# BMS-Shield_rev1.net
KiCad netlist of a schematic drawn in EAGLE
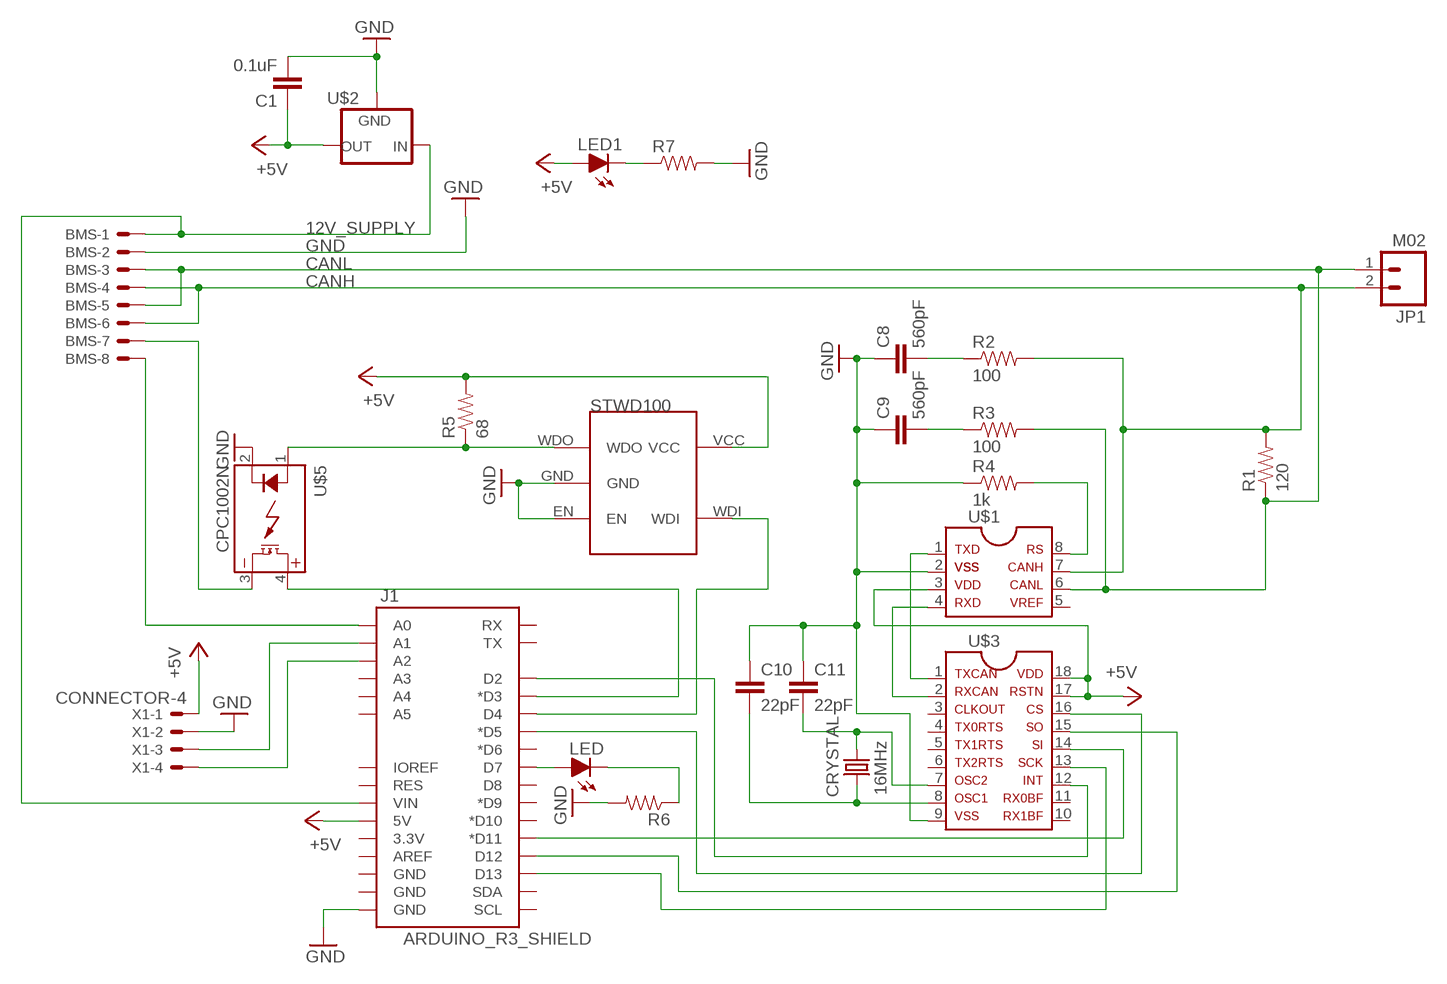
[diagram p0: schematic, sheet 1]

(export (version "E")
  (design (tool "Eeschema 10.0.6"))
  (components
    (comp (ref "BMS")
      (value "MINIFIT_5566-8")
      (footprint "eagle-import:MINIFIT_5566-8")
      (libsource (lib "eagle-import") (part "MINIFIT_5566-8"))
    )
    (comp (ref "C1")
      (value "0.1uF")
      (footprint "eagle-import:0805")
      (libsource (lib "eagle-import") (part "CAP0805"))
    )
    (comp (ref "C8")
      (value "560pF")
      (footprint "eagle-import:0805")
      (libsource (lib "eagle-import") (part "CAP0805"))
    )
    (comp (ref "C9")
      (value "560pF")
      (footprint "eagle-import:0805")
      (libsource (lib "eagle-import") (part "CAP0805"))
    )
    (comp (ref "C10")
      (value "22pF")
      (footprint "eagle-import:0805")
      (libsource (lib "eagle-import") (part "CAP0805"))
    )
    (comp (ref "C11")
      (value "22pF")
      (footprint "eagle-import:0805")
      (libsource (lib "eagle-import") (part "CAP0805"))
    )
    (comp (ref "CRYSTAL")
      (value "16MHz")
      (footprint "eagle-import:HC49UP")
      (libsource (lib "eagle-import") (part "CRYSTALSMD"))
    )
    (comp (ref "J1")
      (value "ARDUINO_R3_SHIELD")
      (footprint "eagle-import:UNO_R3_SHIELD")
      (libsource (lib "eagle-import") (part "ARDUINO_R3_SHIELD"))
    )
    (comp (ref "JP1")
      (value "M02")
      (footprint "eagle-import:1X02")
      (libsource (lib "eagle-import") (part "M02"))
    )
    (comp (ref "LED")
      (value "LED-0805")
      (footprint "eagle-import:LED-805")
      (libsource (lib "eagle-import") (part "LED-0805"))
    )
    (comp (ref "LED1")
      (value "LED-0805")
      (footprint "eagle-import:LED-805")
      (libsource (lib "eagle-import") (part "LED-0805"))
    )
    (comp (ref "R1")
      (value "120")
      (footprint "eagle-import:0805")
      (libsource (lib "eagle-import") (part "RESISTOR0805-RES"))
    )
    (comp (ref "R2")
      (value "100")
      (footprint "eagle-import:0805")
      (libsource (lib "eagle-import") (part "RESISTOR0805-RES"))
    )
    (comp (ref "R3")
      (value "100")
      (footprint "eagle-import:0805")
      (libsource (lib "eagle-import") (part "RESISTOR0805-RES"))
    )
    (comp (ref "R4")
      (value "1k")
      (footprint "eagle-import:0805")
      (libsource (lib "eagle-import") (part "RESISTOR0805-RES"))
    )
    (comp (ref "R5")
      (value "68")
      (footprint "eagle-import:0805")
      (libsource (lib "eagle-import") (part "RESISTOR0805-RES"))
    )
    (comp (ref "R6")
      (value "RESISTOR0805-RES")
      (footprint "eagle-import:0805")
      (libsource (lib "eagle-import") (part "RESISTOR0805-RES"))
    )
    (comp (ref "R7")
      (value "RESISTOR0805-RES")
      (footprint "eagle-import:0805")
      (libsource (lib "eagle-import") (part "RESISTOR0805-RES"))
    )
    (comp (ref "U$1")
      (value "MCP2551")
      (footprint "eagle-import:SOIC-08")
      (libsource (lib "eagle-import") (part "MCP2551"))
    )
    (comp (ref "U$2")
      (value "5VREG_LM340-NLM340MPX-5.0/NOPB")
      (footprint "eagle-import:SOT223")
      (libsource (lib "eagle-import") (part "5VREG_LM340-NLM340MPX-5.0/NOPB"))
    )
    (comp (ref "U$3")
      (value "MCP2515SMD")
      (footprint "eagle-import:SOIC-18W")
      (libsource (lib "eagle-import") (part "MCP2515SMD"))
    )
    (comp (ref "U$4")
      (value "STWD100")
      (footprint "eagle-import:SOT23-5")
      (libsource (lib "eagle-import") (part "STWD100"))
    )
    (comp (ref "U$5")
      (value "CPC1002N")
      (footprint "eagle-import:SOP04")
      (libsource (lib "eagle-import") (part "CPC1002N"))
    )
    (comp (ref "X1")
      (value "CONNECTOR-4")
      (footprint "eagle-import:MINIFIT_5566-4")
      (libsource (lib "eagle-import") (part "CONNECTOR-4"))
    )
  )
  (nets
    (net (code "1") (name "+5V") (class "Default")
      (node (ref "C1") (pin "1") (pinfunction "1_1") (pintype "passive"))
      (node (ref "J1") (pin "5V") (pinfunction "5V_5V") (pintype "bidirectional"))
      (node (ref "LED1") (pin "A") (pinfunction "A_A") (pintype "passive"))
      (node (ref "R5") (pin "2") (pinfunction "2_2") (pintype "passive"))
      (node (ref "U$1") (pin "3") (pinfunction "3_3") (pintype "passive"))
      (node (ref "U$2") (pin "3") (pinfunction "OUT_3") (pintype "output"))
      (node (ref "U$3") (pin "17") (pinfunction "17_17") (pintype "passive"))
      (node (ref "U$3") (pin "18") (pinfunction "18_18") (pintype "passive"))
      (node (ref "U$4") (pin "VCC") (pinfunction "VCC_VCC") (pintype "bidirectional"))
      (node (ref "X1") (pin "1") (pinfunction "S_1") (pintype "passive"))
    )
    (net (code "2") (name "/12V_SUPPLY") (class "Default")
      (node (ref "BMS") (pin "1") (pinfunction "S_1") (pintype "passive"))
      (node (ref "J1") (pin "VIN") (pinfunction "VIN_VIN") (pintype "bidirectional"))
      (node (ref "U$2") (pin "1") (pinfunction "IN_1") (pintype "input"))
    )
    (net (code "3") (name "/CANH") (class "Default")
      (node (ref "BMS") (pin "4") (pinfunction "S_4") (pintype "passive"))
      (node (ref "BMS") (pin "6") (pinfunction "S_6") (pintype "passive"))
      (node (ref "JP1") (pin "2") (pinfunction "2_2") (pintype "passive"))
      (node (ref "R1") (pin "2") (pinfunction "2_2") (pintype "passive"))
      (node (ref "R2") (pin "2") (pinfunction "2_2") (pintype "passive"))
      (node (ref "U$1") (pin "7") (pinfunction "7_7") (pintype "passive"))
    )
    (net (code "4") (name "/CANL") (class "Default")
      (node (ref "BMS") (pin "3") (pinfunction "S_3") (pintype "passive"))
      (node (ref "BMS") (pin "5") (pinfunction "S_5") (pintype "passive"))
      (node (ref "JP1") (pin "1") (pinfunction "1_1") (pintype "passive"))
      (node (ref "R1") (pin "1") (pinfunction "1_1") (pintype "passive"))
      (node (ref "R3") (pin "2") (pinfunction "2_2") (pintype "passive"))
      (node (ref "U$1") (pin "6") (pinfunction "6_6") (pintype "passive"))
    )
    (net (code "5") (name "GND") (class "Default")
      (node (ref "BMS") (pin "2") (pinfunction "S_2") (pintype "passive"))
      (node (ref "C1") (pin "2") (pinfunction "2_2") (pintype "passive"))
      (node (ref "C10") (pin "1") (pinfunction "1_1") (pintype "passive"))
      (node (ref "C11") (pin "1") (pinfunction "1_1") (pintype "passive"))
      (node (ref "C8") (pin "1") (pinfunction "1_1") (pintype "passive"))
      (node (ref "C9") (pin "1") (pinfunction "1_1") (pintype "passive"))
      (node (ref "J1") (pin "GND@0") (pinfunction "GND_GND@0") (pintype "bidirectional"))
      (node (ref "R4") (pin "1") (pinfunction "1_1") (pintype "passive"))
      (node (ref "R6") (pin "2") (pinfunction "2_2") (pintype "passive"))
      (node (ref "R7") (pin "2") (pinfunction "2_2") (pintype "passive"))
      (node (ref "U$1") (pin "2") (pinfunction "2_2") (pintype "passive"))
      (node (ref "U$2") (pin "2") (pinfunction "GND_2") (pintype "input"))
      (node (ref "U$2") (pin "4") (pinfunction "GND_4") (pintype "input"))
      (node (ref "U$3") (pin "9") (pinfunction "9_9") (pintype "passive"))
      (node (ref "U$4") (pin "EN") (pinfunction "EN_EN") (pintype "bidirectional"))
      (node (ref "U$4") (pin "GND") (pinfunction "GND_GND") (pintype "bidirectional"))
      (node (ref "U$5") (pin "2") (pinfunction "CONTROL-_2") (pintype "passive"))
      (node (ref "X1") (pin "2") (pinfunction "S_2") (pintype "passive"))
    )
    (net (code "6") (name "Net-(BMSG-S)") (class "Default")
      (node (ref "BMS") (pin "7") (pinfunction "S_7") (pintype "passive"))
      (node (ref "U$5") (pin "3") (pinfunction "DC-_3") (pintype "passive"))
    )
    (net (code "7") (name "Net-(BMSH-S)") (class "Default")
      (node (ref "BMS") (pin "8") (pinfunction "S_8") (pintype "passive"))
      (node (ref "J1") (pin "A0") (pinfunction "A0_A0") (pintype "bidirectional"))
    )
    (net (code "8") (name "Net-(C8-Pad2)") (class "Default")
      (node (ref "C8") (pin "2") (pinfunction "2_2") (pintype "passive"))
      (node (ref "R2") (pin "1") (pinfunction "1_1") (pintype "passive"))
    )
    (net (code "9") (name "Net-(C9-Pad2)") (class "Default")
      (node (ref "C9") (pin "2") (pinfunction "2_2") (pintype "passive"))
      (node (ref "R3") (pin "1") (pinfunction "1_1") (pintype "passive"))
    )
    (net (code "10") (name "Net-(C10-Pad2)") (class "Default")
      (node (ref "C10") (pin "2") (pinfunction "2_2") (pintype "passive"))
      (node (ref "CRYSTAL") (pin "2") (pinfunction "2_2") (pintype "passive"))
      (node (ref "U$3") (pin "8") (pinfunction "8_8") (pintype "passive"))
    )
    (net (code "11") (name "Net-(C11-Pad2)") (class "Default")
      (node (ref "C11") (pin "2") (pinfunction "2_2") (pintype "passive"))
      (node (ref "CRYSTAL") (pin "1") (pinfunction "1_1") (pintype "passive"))
      (node (ref "U$3") (pin "7") (pinfunction "7_7") (pintype "passive"))
    )
    (net (code "12") (name "Net-(J1-*D3)") (class "Default")
      (node (ref "J1") (pin "D3") (pinfunction "*D3_D3") (pintype "bidirectional"))
      (node (ref "U$5") (pin "4") (pinfunction "DC+_4") (pintype "passive"))
    )
    (net (code "13") (name "Net-(J1-*D5)") (class "Default")
      (node (ref "J1") (pin "D5") (pinfunction "*D5_D5") (pintype "bidirectional"))
      (node (ref "U$3") (pin "16") (pinfunction "16_16") (pintype "passive"))
    )
    (net (code "14") (name "Net-(J1-*D11)") (class "Default")
      (node (ref "J1") (pin "D11") (pinfunction "*D11_D11") (pintype "bidirectional"))
      (node (ref "U$3") (pin "14") (pinfunction "14_14") (pintype "passive"))
    )
    (net (code "15") (name "Net-(J1-PadD2)") (class "Default")
      (node (ref "J1") (pin "D2") (pinfunction "D2_D2") (pintype "bidirectional"))
      (node (ref "U$3") (pin "12") (pinfunction "12_12") (pintype "passive"))
    )
    (net (code "16") (name "Net-(J1-PadD4)") (class "Default")
      (node (ref "J1") (pin "D4") (pinfunction "D4_D4") (pintype "bidirectional"))
      (node (ref "U$4") (pin "WDI") (pinfunction "WDI_WDI") (pintype "bidirectional"))
    )
    (net (code "17") (name "Net-(J1-PadD7)") (class "Default")
      (node (ref "J1") (pin "D7") (pinfunction "D7_D7") (pintype "bidirectional"))
      (node (ref "LED") (pin "A") (pinfunction "A_A") (pintype "passive"))
    )
    (net (code "18") (name "Net-(J1-PadD12)") (class "Default")
      (node (ref "J1") (pin "D12") (pinfunction "D12_D12") (pintype "bidirectional"))
      (node (ref "U$3") (pin "15") (pinfunction "15_15") (pintype "passive"))
    )
    (net (code "19") (name "Net-(J1-PadD13)") (class "Default")
      (node (ref "J1") (pin "D13") (pinfunction "D13_D13") (pintype "bidirectional"))
      (node (ref "U$3") (pin "13") (pinfunction "13_13") (pintype "passive"))
    )
    (net (code "20") (name "Net-(LED-PadC)") (class "Default")
      (node (ref "LED") (pin "C") (pinfunction "C_C") (pintype "passive"))
      (node (ref "R6") (pin "1") (pinfunction "1_1") (pintype "passive"))
    )
    (net (code "21") (name "Net-(LED1-PadC)") (class "Default")
      (node (ref "LED1") (pin "C") (pinfunction "C_C") (pintype "passive"))
      (node (ref "R7") (pin "1") (pinfunction "1_1") (pintype "passive"))
    )
    (net (code "22") (name "Net-(R4-Pad2)") (class "Default")
      (node (ref "R4") (pin "2") (pinfunction "2_2") (pintype "passive"))
      (node (ref "U$1") (pin "8") (pinfunction "8_8") (pintype "passive"))
    )
    (net (code "23") (name "Net-(U$1-Pad1)") (class "Default")
      (node (ref "U$1") (pin "1") (pinfunction "1_1") (pintype "passive"))
      (node (ref "U$3") (pin "1") (pinfunction "1_1") (pintype "passive"))
    )
    (net (code "24") (name "Net-(U$1-Pad4)") (class "Default")
      (node (ref "U$1") (pin "4") (pinfunction "4_4") (pintype "passive"))
      (node (ref "U$3") (pin "2") (pinfunction "2_2") (pintype "passive"))
    )
    (net (code "25") (name "Net-(U$5-CONTROL+)") (class "Default")
      (node (ref "R5") (pin "1") (pinfunction "1_1") (pintype "passive"))
      (node (ref "U$4") (pin "WDO") (pinfunction "WDO_WDO") (pintype "bidirectional"))
      (node (ref "U$5") (pin "1") (pinfunction "CONTROL+_1") (pintype "passive"))
    )
    (net (code "26") (name "Net-(X1C-S)") (class "Default")
      (node (ref "J1") (pin "A1") (pinfunction "A1_A1") (pintype "bidirectional"))
      (node (ref "X1") (pin "3") (pinfunction "S_3") (pintype "passive"))
    )
    (net (code "27") (name "Net-(X1D-S)") (class "Default")
      (node (ref "J1") (pin "A2") (pinfunction "A2_A2") (pintype "bidirectional"))
      (node (ref "X1") (pin "4") (pinfunction "S_4") (pintype "passive"))
    )
    (net (code "28") (name "unconnected-(J1-*D6-PadD6)") (class "Default")
      (node (ref "J1") (pin "D6") (pinfunction "*D6_D6") (pintype "bidirectional"))
    )
    (net (code "29") (name "unconnected-(J1-*D9-PadD9)") (class "Default")
      (node (ref "J1") (pin "D9") (pinfunction "*D9_D9") (pintype "bidirectional"))
    )
    (net (code "30") (name "unconnected-(J1-*D10-PadD10)") (class "Default")
      (node (ref "J1") (pin "D10") (pinfunction "*D10_D10") (pintype "bidirectional"))
    )
    (net (code "31") (name "unconnected-(J1-GND-PadGND@1)") (class "Default")
      (node (ref "J1") (pin "GND@1") (pinfunction "GND_GND@1") (pintype "bidirectional"))
    )
    (net (code "32") (name "unconnected-(J1-GND-PadGND@2)") (class "Default")
      (node (ref "J1") (pin "GND@2") (pinfunction "GND_GND@2") (pintype "bidirectional"))
    )
    (net (code "33") (name "unconnected-(J1-Pad3.3V)") (class "Default")
      (node (ref "J1") (pin "3.3V") (pinfunction "3.3V_3.3V") (pintype "bidirectional"))
    )
    (net (code "34") (name "unconnected-(J1-PadA3)") (class "Default")
      (node (ref "J1") (pin "A3") (pinfunction "A3_A3") (pintype "bidirectional"))
    )
    (net (code "35") (name "unconnected-(J1-PadA4)") (class "Default")
      (node (ref "J1") (pin "A4") (pinfunction "A4_A4") (pintype "bidirectional"))
    )
    (net (code "36") (name "unconnected-(J1-PadA5)") (class "Default")
      (node (ref "J1") (pin "A5") (pinfunction "A5_A5") (pintype "bidirectional"))
    )
    (net (code "37") (name "unconnected-(J1-PadAREF)") (class "Default")
      (node (ref "J1") (pin "AREF") (pinfunction "AREF_AREF") (pintype "bidirectional"))
    )
    (net (code "38") (name "unconnected-(J1-PadD8)") (class "Default")
      (node (ref "J1") (pin "D8") (pinfunction "D8_D8") (pintype "bidirectional"))
    )
    (net (code "39") (name "unconnected-(J1-PadIOREF)") (class "Default")
      (node (ref "J1") (pin "IOREF") (pinfunction "IOREF_IOREF") (pintype "bidirectional"))
    )
    (net (code "40") (name "unconnected-(J1-PadRES)") (class "Default")
      (node (ref "J1") (pin "RES") (pinfunction "RES_RES") (pintype "bidirectional"))
    )
    (net (code "41") (name "unconnected-(J1-PadRX)") (class "Default")
      (node (ref "J1") (pin "RX") (pinfunction "RX_RX") (pintype "bidirectional"))
    )
    (net (code "42") (name "unconnected-(J1-PadSCL)") (class "Default")
      (node (ref "J1") (pin "SCL") (pinfunction "SCL_SCL") (pintype "bidirectional"))
    )
    (net (code "43") (name "unconnected-(J1-PadSDA)") (class "Default")
      (node (ref "J1") (pin "SDA") (pinfunction "SDA_SDA") (pintype "bidirectional"))
    )
    (net (code "44") (name "unconnected-(J1-PadTX)") (class "Default")
      (node (ref "J1") (pin "TX") (pinfunction "TX_TX") (pintype "bidirectional"))
    )
    (net (code "45") (name "unconnected-(U$1-Pad5)") (class "Default")
      (node (ref "U$1") (pin "5") (pinfunction "5_5") (pintype "passive"))
    )
    (net (code "46") (name "unconnected-(U$3-Pad3)") (class "Default")
      (node (ref "U$3") (pin "3") (pinfunction "3_3") (pintype "passive"))
    )
    (net (code "47") (name "unconnected-(U$3-Pad4)") (class "Default")
      (node (ref "U$3") (pin "4") (pinfunction "4_4") (pintype "passive"))
    )
    (net (code "48") (name "unconnected-(U$3-Pad5)") (class "Default")
      (node (ref "U$3") (pin "5") (pinfunction "5_5") (pintype "passive"))
    )
    (net (code "49") (name "unconnected-(U$3-Pad6)") (class "Default")
      (node (ref "U$3") (pin "6") (pinfunction "6_6") (pintype "passive"))
    )
    (net (code "50") (name "unconnected-(U$3-Pad10)") (class "Default")
      (node (ref "U$3") (pin "10") (pinfunction "10_10") (pintype "passive"))
    )
    (net (code "51") (name "unconnected-(U$3-Pad11)") (class "Default")
      (node (ref "U$3") (pin "11") (pinfunction "11_11") (pintype "passive"))
    )
  )
)
